# cpu-fast.net
KiCad netlist of a schematic drawn in EAGLE
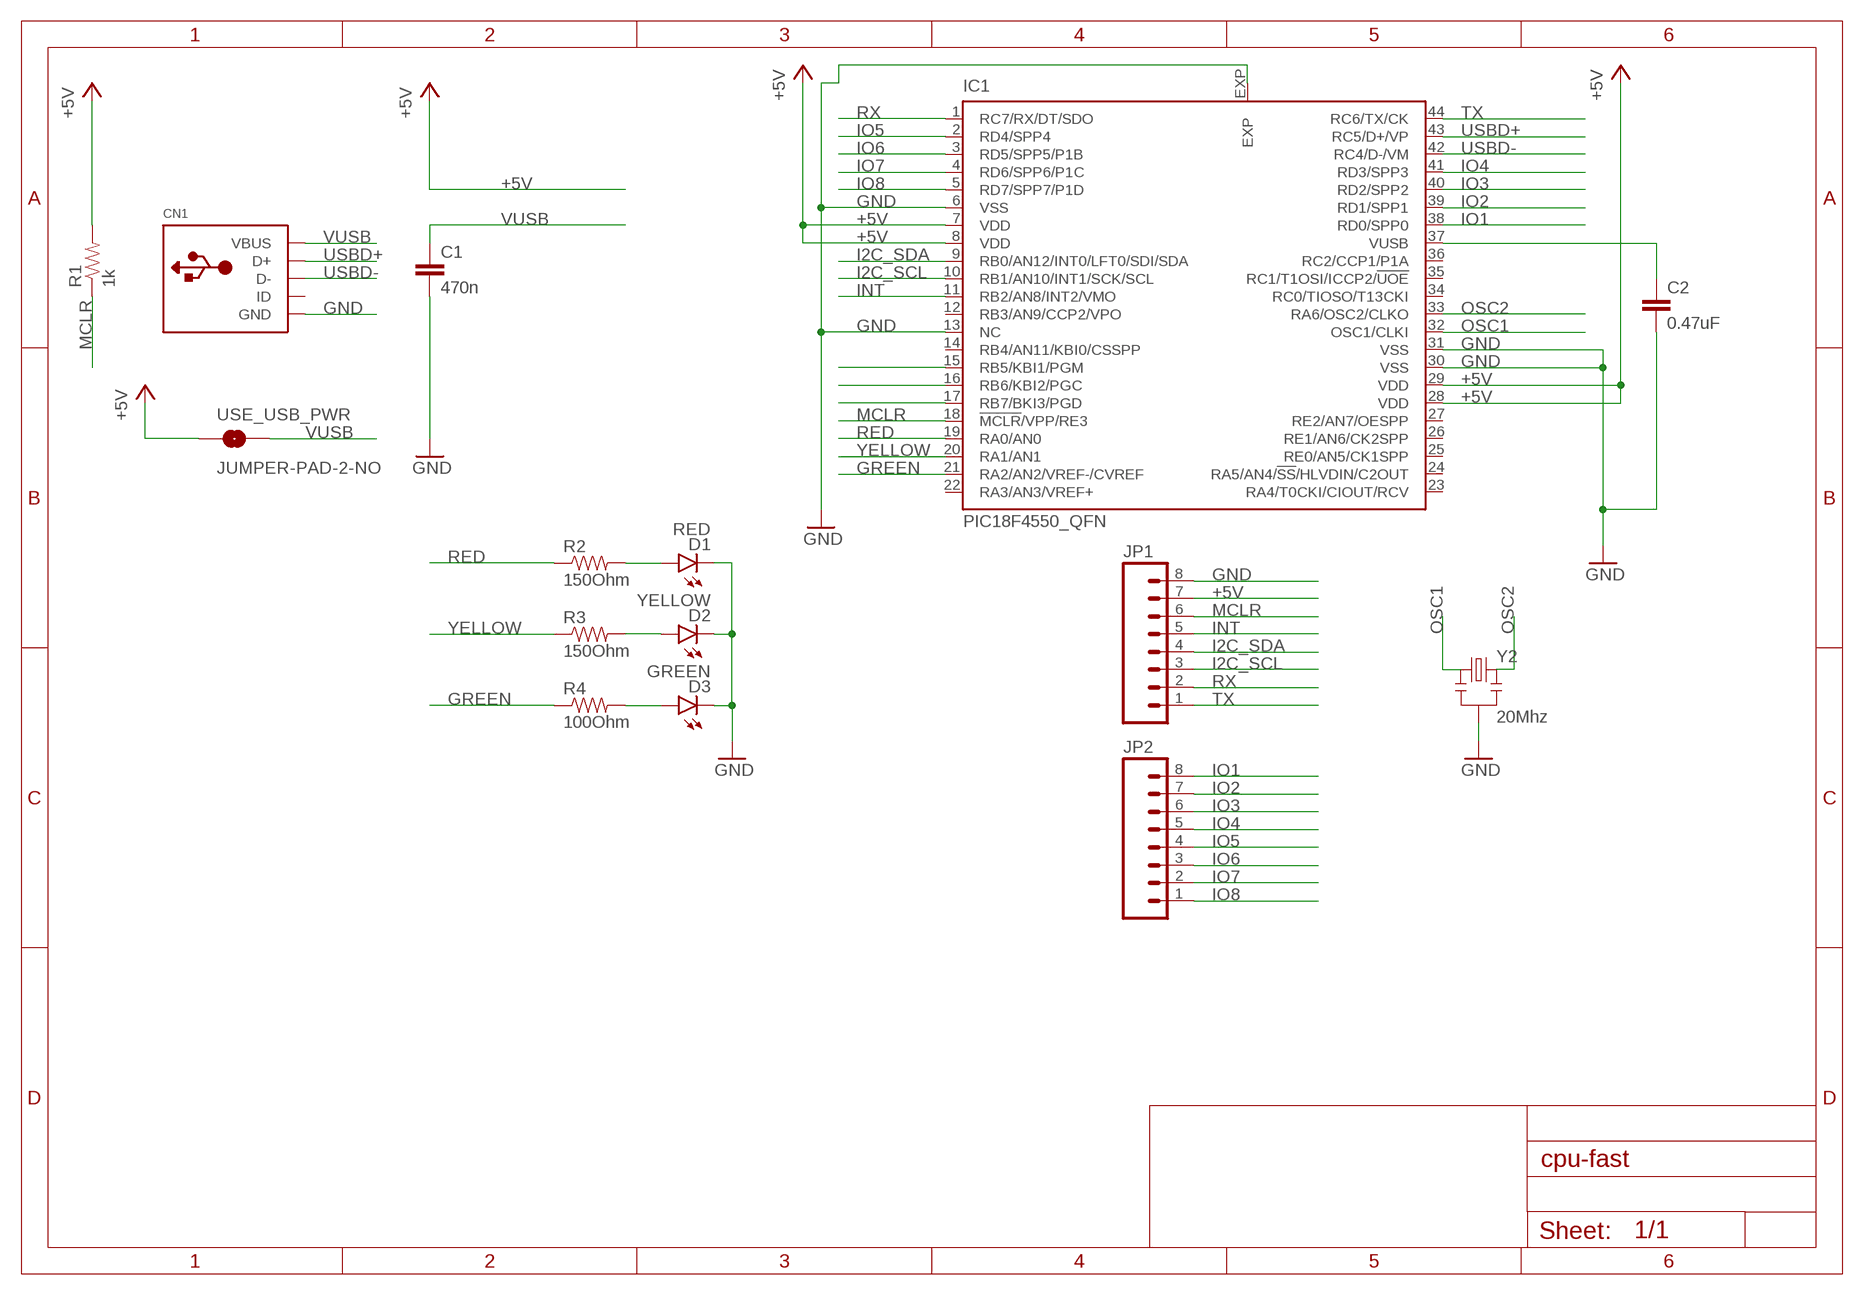
[diagram p0: schematic, sheet 1]

(export (version "E")
  (design (tool "Eeschema 10.0.6"))
  (components
    (comp (ref "C1")
      (value "470n")
      (footprint "eagle-import:C0805K")
      (libsource (lib "eagle-import") (part "C-EUC0805K"))
    )
    (comp (ref "C2")
      (value "0.47uF")
      (footprint "eagle-import:0603-CAP")
      (libsource (lib "eagle-import") (part "0.22UF-25V-10%(0603)"))
    )
    (comp (ref "CN1")
      (value "USBMINIB")
      (footprint "eagle-import:USB-MINIB")
      (libsource (lib "eagle-import") (part "USBMINIB"))
    )
    (comp (ref "D1")
      (value "RED")
      (footprint "eagle-import:LED-0603")
      (libsource (lib "eagle-import") (part "LED-RED0603"))
    )
    (comp (ref "D2")
      (value "YELLOW")
      (footprint "eagle-import:LED-0603")
      (libsource (lib "eagle-import") (part "LED-YELLOW0603"))
    )
    (comp (ref "D3")
      (value "GREEN")
      (footprint "eagle-import:LED-0603")
      (libsource (lib "eagle-import") (part "LED-GREEN0603"))
    )
    (comp (ref "IC1")
      (value "PIC18F4550_QFN")
      (footprint "eagle-import:QFN44ML8X8")
      (fields (field (name "MF") "MICROCHIP") (field (name "MPN") "PIC18F4550-I/ML"))
      (libsource (lib "eagle-import") (part "PIC18F4_QFN550"))
    )
    (comp (ref "JP1")
      (value "M081X08")
      (footprint "eagle-import:1X08")
      (libsource (lib "eagle-import") (part "M081X08"))
    )
    (comp (ref "JP2")
      (value "M081X08")
      (footprint "eagle-import:1X08")
      (libsource (lib "eagle-import") (part "M081X08"))
    )
    (comp (ref "R1")
      (value "1k")
      (footprint "eagle-import:0402-RES")
      (libsource (lib "eagle-import") (part "RESISTOR0402-RES"))
    )
    (comp (ref "R2")
      (value "150Ohm")
      (footprint "eagle-import:0402-RES")
      (libsource (lib "eagle-import") (part "RESISTOR0402-RES"))
    )
    (comp (ref "R3")
      (value "150Ohm")
      (footprint "eagle-import:0402-RES")
      (libsource (lib "eagle-import") (part "RESISTOR0402-RES"))
    )
    (comp (ref "R4")
      (value "100Ohm")
      (footprint "eagle-import:0402-RES")
      (libsource (lib "eagle-import") (part "RESISTOR0402-RES"))
    )
    (comp (ref "USE_USB_PWR")
      (value "JUMPER-PAD-2-NO")
      (footprint "eagle-import:PAD-JUMPER-2-NO_NO_SILK")
      (libsource (lib "eagle-import") (part "JUMPER-PAD-2-NO"))
    )
    (comp (ref "Y2")
      (value "20Mhz")
      (footprint "eagle-import:RESONATOR-SMD")
      (libsource (lib "eagle-import") (part "RESONATOR16MHZ"))
    )
  )
  (nets
    (net (code "1") (name "+5V") (class "Default")
      (node (ref "IC1") (pin "28") (pinfunction "VDD_28") (pintype "power_in"))
      (node (ref "IC1") (pin "29") (pinfunction "VDD_29") (pintype "power_in"))
      (node (ref "IC1") (pin "7") (pinfunction "VDD_7") (pintype "power_in"))
      (node (ref "IC1") (pin "8") (pinfunction "VDD_8") (pintype "power_in"))
      (node (ref "JP1") (pin "7") (pinfunction "7_7") (pintype "passive"))
      (node (ref "R1") (pin "2") (pinfunction "2_2") (pintype "passive"))
      (node (ref "USE_USB_PWR") (pin "1") (pinfunction "1_1") (pintype "passive"))
    )
    (net (code "2") (name "/GREEN") (class "Default")
      (node (ref "IC1") (pin "21") (pinfunction "RA2/AN2/VREF-/CVREF_21") (pintype "bidirectional"))
      (node (ref "R4") (pin "1") (pinfunction "1_1") (pintype "passive"))
    )
    (net (code "3") (name "/I2C_SCL") (class "Default")
      (node (ref "IC1") (pin "10") (pinfunction "RB1/AN10/INT1/SCK/SCL_10") (pintype "bidirectional"))
      (node (ref "JP1") (pin "3") (pinfunction "3_3") (pintype "passive"))
    )
    (net (code "4") (name "/I2C_SDA") (class "Default")
      (node (ref "IC1") (pin "9") (pinfunction "RB0/AN12/INT0/LFT0/SDI/SDA_9") (pintype "bidirectional"))
      (node (ref "JP1") (pin "4") (pinfunction "4_4") (pintype "passive"))
    )
    (net (code "5") (name "/INT") (class "Default")
      (node (ref "IC1") (pin "11") (pinfunction "RB2/AN8/INT2/VMO_11") (pintype "bidirectional"))
      (node (ref "JP1") (pin "5") (pinfunction "5_5") (pintype "passive"))
    )
    (net (code "6") (name "/IO1") (class "Default")
      (node (ref "IC1") (pin "38") (pinfunction "RD0/SPP0_38") (pintype "bidirectional"))
      (node (ref "JP2") (pin "8") (pinfunction "8_8") (pintype "passive"))
    )
    (net (code "7") (name "/IO2") (class "Default")
      (node (ref "IC1") (pin "39") (pinfunction "RD1/SPP1_39") (pintype "bidirectional"))
      (node (ref "JP2") (pin "7") (pinfunction "7_7") (pintype "passive"))
    )
    (net (code "8") (name "/IO3") (class "Default")
      (node (ref "IC1") (pin "40") (pinfunction "RD2/SPP2_40") (pintype "bidirectional"))
      (node (ref "JP2") (pin "6") (pinfunction "6_6") (pintype "passive"))
    )
    (net (code "9") (name "/IO4") (class "Default")
      (node (ref "IC1") (pin "41") (pinfunction "RD3/SPP3_41") (pintype "bidirectional"))
      (node (ref "JP2") (pin "5") (pinfunction "5_5") (pintype "passive"))
    )
    (net (code "10") (name "/IO5") (class "Default")
      (node (ref "IC1") (pin "2") (pinfunction "RD4/SPP4_2") (pintype "bidirectional"))
      (node (ref "JP2") (pin "4") (pinfunction "4_4") (pintype "passive"))
    )
    (net (code "11") (name "/IO6") (class "Default")
      (node (ref "IC1") (pin "3") (pinfunction "RD5/SPP5/P1B_3") (pintype "bidirectional"))
      (node (ref "JP2") (pin "3") (pinfunction "3_3") (pintype "passive"))
    )
    (net (code "12") (name "/IO7") (class "Default")
      (node (ref "IC1") (pin "4") (pinfunction "RD6/SPP6/P1C_4") (pintype "bidirectional"))
      (node (ref "JP2") (pin "2") (pinfunction "2_2") (pintype "passive"))
    )
    (net (code "13") (name "/IO8") (class "Default")
      (node (ref "IC1") (pin "5") (pinfunction "RD7/SPP7/P1D_5") (pintype "bidirectional"))
      (node (ref "JP2") (pin "1") (pinfunction "1_1") (pintype "passive"))
    )
    (net (code "14") (name "/MCLR") (class "Default")
      (node (ref "IC1") (pin "18") (pinfunction "~{MCLR}/VPP/RE3_18") (pintype "input"))
      (node (ref "JP1") (pin "6") (pinfunction "6_6") (pintype "passive"))
      (node (ref "R1") (pin "1") (pinfunction "1_1") (pintype "passive"))
    )
    (net (code "15") (name "/OSC1") (class "Default")
      (node (ref "IC1") (pin "32") (pinfunction "OSC1/CLKI_32") (pintype "input"))
      (node (ref "Y2") (pin "1") (pinfunction "1_1") (pintype "passive"))
    )
    (net (code "16") (name "/OSC2") (class "Default")
      (node (ref "IC1") (pin "33") (pinfunction "RA6/OSC2/CLKO_33") (pintype "output"))
      (node (ref "Y2") (pin "3") (pinfunction "3_3") (pintype "passive"))
    )
    (net (code "17") (name "/RED") (class "Default")
      (node (ref "IC1") (pin "19") (pinfunction "RA0/AN0_19") (pintype "bidirectional"))
      (node (ref "R2") (pin "1") (pinfunction "1_1") (pintype "passive"))
    )
    (net (code "18") (name "/RX") (class "Default")
      (node (ref "IC1") (pin "1") (pinfunction "RC7/RX/DT/SDO_1") (pintype "bidirectional"))
      (node (ref "JP1") (pin "2") (pinfunction "2_2") (pintype "passive"))
    )
    (net (code "19") (name "/TX") (class "Default")
      (node (ref "IC1") (pin "44") (pinfunction "RC6/TX/CK_44") (pintype "bidirectional"))
      (node (ref "JP1") (pin "1") (pinfunction "1_1") (pintype "passive"))
    )
    (net (code "20") (name "/USBD+") (class "Default")
      (node (ref "CN1") (pin "D+") (pinfunction "D+_D+") (pintype "bidirectional"))
      (node (ref "IC1") (pin "43") (pinfunction "RC5/D+/VP_43") (pintype "bidirectional"))
    )
    (net (code "21") (name "/USBD-") (class "Default")
      (node (ref "CN1") (pin "D-") (pinfunction "D-_D-") (pintype "bidirectional"))
      (node (ref "IC1") (pin "42") (pinfunction "RC4/D-/VM_42") (pintype "bidirectional"))
    )
    (net (code "22") (name "/VUSB") (class "Default")
      (node (ref "C1") (pin "1") (pinfunction "1_1") (pintype "passive"))
      (node (ref "CN1") (pin "VBUS") (pinfunction "VBUS_VBUS") (pintype "power_in"))
      (node (ref "USE_USB_PWR") (pin "2") (pinfunction "2_2") (pintype "passive"))
    )
    (net (code "23") (name "/YELLOW") (class "Default")
      (node (ref "IC1") (pin "20") (pinfunction "RA1/AN1_20") (pintype "bidirectional"))
      (node (ref "R3") (pin "1") (pinfunction "1_1") (pintype "passive"))
    )
    (net (code "24") (name "GND") (class "Default")
      (node (ref "C1") (pin "2") (pinfunction "2_2") (pintype "passive"))
      (node (ref "C2") (pin "2") (pinfunction "2_2") (pintype "passive"))
      (node (ref "CN1") (pin "GND") (pinfunction "GND_GND") (pintype "power_in"))
      (node (ref "D1") (pin "C") (pinfunction "C_C") (pintype "passive"))
      (node (ref "D2") (pin "C") (pinfunction "C_C") (pintype "passive"))
      (node (ref "D3") (pin "C") (pinfunction "C_C") (pintype "passive"))
      (node (ref "IC1") (pin "13") (pinfunction "NC_13") (pintype "bidirectional"))
      (node (ref "IC1") (pin "30") (pinfunction "VSS_30") (pintype "power_in"))
      (node (ref "IC1") (pin "31") (pinfunction "VSS_31") (pintype "power_in"))
      (node (ref "IC1") (pin "6") (pinfunction "VSS_6") (pintype "power_in"))
      (node (ref "IC1") (pin "EXP") (pinfunction "EXP_EXP") (pintype "passive"))
      (node (ref "JP1") (pin "8") (pinfunction "8_8") (pintype "passive"))
      (node (ref "Y2") (pin "2") (pinfunction "2_2") (pintype "passive"))
    )
    (net (code "25") (name "Net-(D1-PadA)") (class "Default")
      (node (ref "D1") (pin "A") (pinfunction "A_A") (pintype "passive"))
      (node (ref "R2") (pin "2") (pinfunction "2_2") (pintype "passive"))
    )
    (net (code "26") (name "Net-(D2-PadA)") (class "Default")
      (node (ref "D2") (pin "A") (pinfunction "A_A") (pintype "passive"))
      (node (ref "R3") (pin "2") (pinfunction "2_2") (pintype "passive"))
    )
    (net (code "27") (name "Net-(D3-PadA)") (class "Default")
      (node (ref "D3") (pin "A") (pinfunction "A_A") (pintype "passive"))
      (node (ref "R4") (pin "2") (pinfunction "2_2") (pintype "passive"))
    )
    (net (code "28") (name "Net-(IC1-VUSB)") (class "Default")
      (node (ref "C2") (pin "1") (pinfunction "1_1") (pintype "passive"))
      (node (ref "IC1") (pin "37") (pinfunction "VUSB_37") (pintype "bidirectional"))
    )
    (net (code "29") (name "unconnected-(CN1-PadID)") (class "Default")
      (node (ref "CN1") (pin "ID") (pinfunction "ID_ID") (pintype "bidirectional"))
    )
    (net (code "30") (name "unconnected-(IC1-RA3{slash}AN3{slash}VREF+-Pad22)") (class "Default")
      (node (ref "IC1") (pin "22") (pinfunction "RA3/AN3/VREF+_22") (pintype "bidirectional"))
    )
    (net (code "31") (name "unconnected-(IC1-RA4{slash}T0CKI{slash}CIOUT{slash}RCV-Pad23)") (class "Default")
      (node (ref "IC1") (pin "23") (pinfunction "RA4/T0CKI/CIOUT/RCV_23") (pintype "bidirectional"))
    )
    (net (code "32") (name "unconnected-(IC1-RA5{slash}AN4{slash}~{SS}{slash}HLVDIN{slash}C2OUT-Pad24)") (class "Default")
      (node (ref "IC1") (pin "24") (pinfunction "RA5/AN4/~{SS}/HLVDIN/C2OUT_24") (pintype "bidirectional"))
    )
    (net (code "33") (name "unconnected-(IC1-RB3{slash}AN9{slash}CCP2{slash}VPO-Pad12)") (class "Default")
      (node (ref "IC1") (pin "12") (pinfunction "RB3/AN9/CCP2/VPO_12") (pintype "bidirectional"))
    )
    (net (code "34") (name "unconnected-(IC1-RB4{slash}AN11{slash}KBI0{slash}CSSPP-Pad14)") (class "Default")
      (node (ref "IC1") (pin "14") (pinfunction "RB4/AN11/KBI0/CSSPP_14") (pintype "bidirectional"))
    )
    (net (code "35") (name "unconnected-(IC1-RB5{slash}KBI1{slash}PGM-Pad15)") (class "Default")
      (node (ref "IC1") (pin "15") (pinfunction "RB5/KBI1/PGM_15") (pintype "bidirectional"))
    )
    (net (code "36") (name "unconnected-(IC1-RB6{slash}KBI2{slash}PGC-Pad16)") (class "Default")
      (node (ref "IC1") (pin "16") (pinfunction "RB6/KBI2/PGC_16") (pintype "bidirectional"))
    )
    (net (code "37") (name "unconnected-(IC1-RB7{slash}BKI3{slash}PGD-Pad17)") (class "Default")
      (node (ref "IC1") (pin "17") (pinfunction "RB7/BKI3/PGD_17") (pintype "bidirectional"))
    )
    (net (code "38") (name "unconnected-(IC1-RC0{slash}TIOSO{slash}T13CKI-Pad34)") (class "Default")
      (node (ref "IC1") (pin "34") (pinfunction "RC0/TIOSO/T13CKI_34") (pintype "bidirectional"))
    )
    (net (code "39") (name "unconnected-(IC1-RC1{slash}T1OSI{slash}ICCP2{slash}~{UOE}-Pad35)") (class "Default")
      (node (ref "IC1") (pin "35") (pinfunction "RC1/T1OSI/ICCP2/~{UOE}_35") (pintype "bidirectional"))
    )
    (net (code "40") (name "unconnected-(IC1-RC2{slash}CCP1{slash}P1A-Pad36)") (class "Default")
      (node (ref "IC1") (pin "36") (pinfunction "RC2/CCP1/P1A_36") (pintype "bidirectional"))
    )
    (net (code "41") (name "unconnected-(IC1-RE0{slash}AN5{slash}CK1SPP-Pad25)") (class "Default")
      (node (ref "IC1") (pin "25") (pinfunction "RE0/AN5/CK1SPP_25") (pintype "bidirectional"))
    )
    (net (code "42") (name "unconnected-(IC1-RE1{slash}AN6{slash}CK2SPP-Pad26)") (class "Default")
      (node (ref "IC1") (pin "26") (pinfunction "RE1/AN6/CK2SPP_26") (pintype "bidirectional"))
    )
    (net (code "43") (name "unconnected-(IC1-RE2{slash}AN7{slash}OESPP-Pad27)") (class "Default")
      (node (ref "IC1") (pin "27") (pinfunction "RE2/AN7/OESPP_27") (pintype "bidirectional"))
    )
  )
)
